# xiao-ble-e22-pcb-only.net
KiCad netlist of a schematic drawn in EAGLE
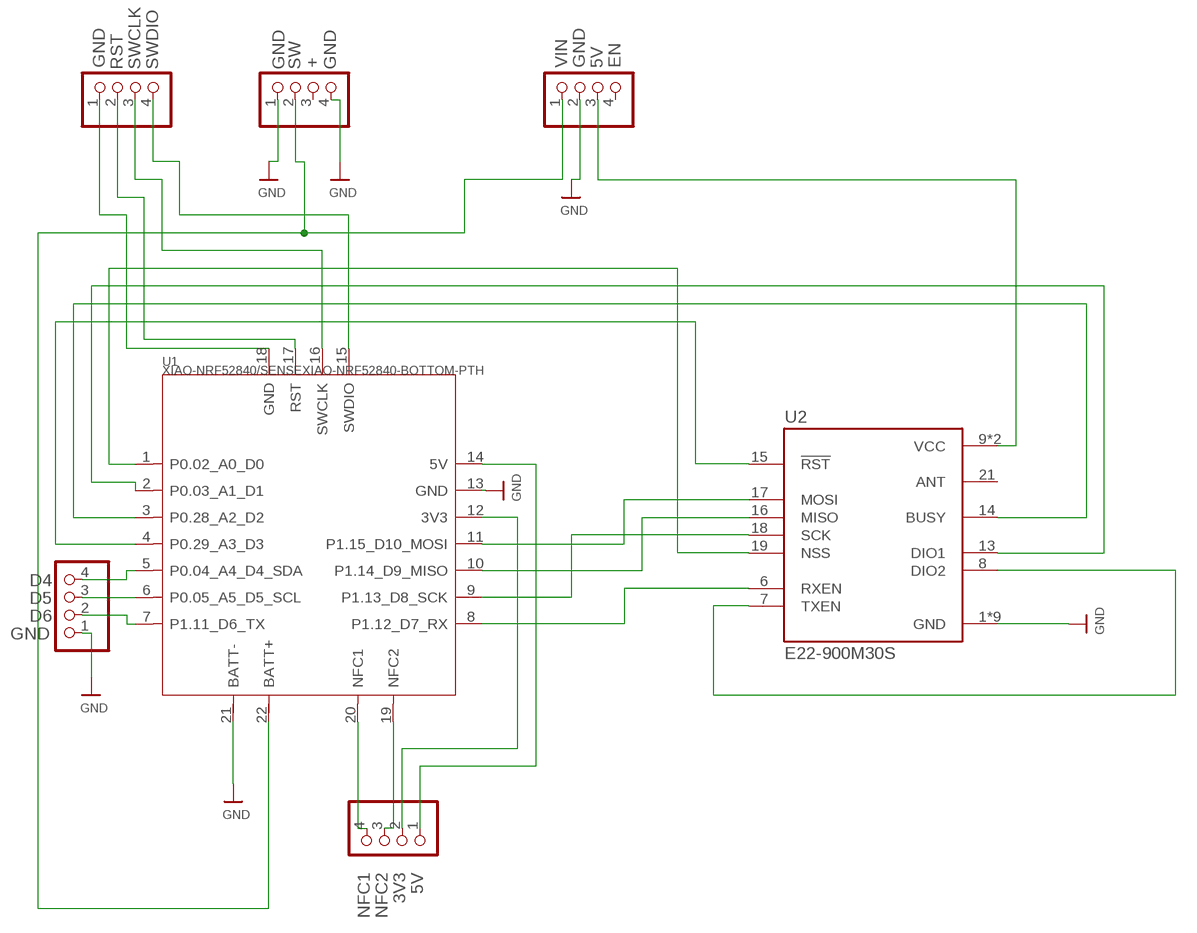
[diagram p0: schematic, sheet 1]

(export (version "E")
  (design (tool "Eeschema 10.0.6"))
  (components
    (comp (ref "JP1")
      (value "MiniBoost Breakout")
      (footprint "eagle-import:PADS-4")
      (fields
        (field (name "PIN_1") "VIN")
        (field (name "PIN_2") "GND")
        (field (name "PIN_3") "5V")
        (field (name "PIN_4") "EN")
      )
      (libsource (lib "eagle-import") (part "PADS-4"))
    )
    (comp (ref "JP2")
      (value "GPIO Breakout 1")
      (footprint "eagle-import:PADS-4")
      (fields
        (field (name "PIN_1") "5V")
        (field (name "PIN_2") "3V3")
        (field (name "PIN_3") "NFC2")
        (field (name "PIN_4") "NFC1")
      )
      (libsource (lib "eagle-import") (part "PADS-4"))
    )
    (comp (ref "JP3")
      (value "GPIO Breakout 2")
      (footprint "eagle-import:PADS-4")
      (fields
        (field (name "PIN_1") "GND")
        (field (name "PIN_2") "D6")
        (field (name "PIN_3") "D5")
        (field (name "PIN_4") "D4")
      )
      (libsource (lib "eagle-import") (part "PADS-4"))
    )
    (comp (ref "JP4")
      (value "JST + Switch Breakout")
      (footprint "eagle-import:PADS-4")
      (fields
        (field (name "PIN_1") "GND")
        (field (name "PIN_2") "+")
        (field (name "PIN_3") "SW")
        (field (name "PIN_4") "GND")
      )
      (libsource (lib "eagle-import") (part "PADS-4"))
    )
    (comp (ref "JP5")
      (value "GPIO Breakout 2")
      (footprint "eagle-import:PADS-4")
      (fields
        (field (name "PIN_1") "GND")
        (field (name "PIN_2") "RST")
        (field (name "PIN_3") "SWCLK")
        (field (name "PIN_4") "SWDIO")
      )
      (libsource (lib "eagle-import") (part "PADS-4"))
    )
    (comp (ref "U1")
      (value "XIAO-NRF52840/SENSEXIAO-NRF52840-BOTTOM-PTH")
      (footprint "eagle-import:XIAO-NRF52840_SENSE-MODULE14P-2.54-21X17.8MM-BOTTOM-PTH")
      (libsource (lib "eagle-import") (part "XIAO-NRF52840/SENSEXIAO-NRF52840-BOTTOM-PTH"))
    )
    (comp (ref "U2")
      (value "E22-900M30S")
      (footprint "eagle-import:XCVR_E22-900M30S")
      (fields (field (name "MF") "EBYTE"))
      (libsource (lib "eagle-import") (part "E22-900M30S"))
    )
  )
  (nets
    (net (code "1") (name "GND") (class "Default")
      (node (ref "JP1") (pin "2") (pinfunction "2_2") (pintype "passive"))
      (node (ref "JP3") (pin "1") (pinfunction "1_1") (pintype "passive"))
      (node (ref "JP4") (pin "1") (pinfunction "1_1") (pintype "passive"))
      (node (ref "JP4") (pin "4") (pinfunction "4_4") (pintype "passive"))
      (node (ref "U1") (pin "13") (pinfunction "GND_13") (pintype "bidirectional"))
      (node (ref "U1") (pin "21") (pinfunction "BATT-_21") (pintype "bidirectional"))
      (node (ref "U2") (pin "1") (pinfunction "GND_1") (pintype "power_in"))
      (node (ref "U2") (pin "11") (pinfunction "GND_11") (pintype "power_in"))
      (node (ref "U2") (pin "12") (pinfunction "GND_12") (pintype "power_in"))
      (node (ref "U2") (pin "2") (pinfunction "GND_2") (pintype "power_in"))
      (node (ref "U2") (pin "20") (pinfunction "GND_20") (pintype "power_in"))
      (node (ref "U2") (pin "22") (pinfunction "GND_22") (pintype "power_in"))
      (node (ref "U2") (pin "3") (pinfunction "GND_3") (pintype "power_in"))
      (node (ref "U2") (pin "4") (pinfunction "GND_4") (pintype "power_in"))
      (node (ref "U2") (pin "5") (pinfunction "GND_5") (pintype "power_in"))
    )
    (net (code "2") (name "Net-(JP1-Pad3)") (class "Default")
      (node (ref "JP1") (pin "3") (pinfunction "3_3") (pintype "passive"))
      (node (ref "U2") (pin "10") (pinfunction "VCC_10") (pintype "power_in"))
      (node (ref "U2") (pin "9") (pinfunction "VCC_9") (pintype "power_in"))
    )
    (net (code "3") (name "Net-(JP5-Pad1)") (class "Default")
      (node (ref "JP5") (pin "1") (pinfunction "1_1") (pintype "passive"))
      (node (ref "U1") (pin "18") (pinfunction "GND_18") (pintype "bidirectional"))
    )
    (net (code "4") (name "Net-(U1-3V3)") (class "Default")
      (node (ref "JP2") (pin "2") (pinfunction "2_2") (pintype "passive"))
      (node (ref "U1") (pin "12") (pinfunction "3V3_12") (pintype "bidirectional"))
    )
    (net (code "5") (name "Net-(U1-5V)") (class "Default")
      (node (ref "JP2") (pin "1") (pinfunction "1_1") (pintype "passive"))
      (node (ref "U1") (pin "14") (pinfunction "5V_14") (pintype "bidirectional"))
    )
    (net (code "6") (name "Net-(U1-BATT+)") (class "Default")
      (node (ref "JP1") (pin "1") (pinfunction "1_1") (pintype "passive"))
      (node (ref "JP4") (pin "2") (pinfunction "2_2") (pintype "passive"))
      (node (ref "U1") (pin "22") (pinfunction "BATT+_22") (pintype "bidirectional"))
    )
    (net (code "7") (name "Net-(U1-NFC1)") (class "Default")
      (node (ref "JP2") (pin "4") (pinfunction "4_4") (pintype "passive"))
      (node (ref "U1") (pin "20") (pinfunction "NFC1_20") (pintype "bidirectional"))
    )
    (net (code "8") (name "Net-(U1-NFC2)") (class "Default")
      (node (ref "JP2") (pin "3") (pinfunction "3_3") (pintype "passive"))
      (node (ref "U1") (pin "19") (pinfunction "NFC2_19") (pintype "bidirectional"))
    )
    (net (code "9") (name "Net-(U1-P0.02_A0_D0)") (class "Default")
      (node (ref "U1") (pin "1") (pinfunction "P0.02_A0_D0_1") (pintype "bidirectional"))
      (node (ref "U2") (pin "19") (pinfunction "NSS_19") (pintype "input"))
    )
    (net (code "10") (name "Net-(U1-P0.03_A1_D1)") (class "Default")
      (node (ref "U1") (pin "2") (pinfunction "P0.03_A1_D1_2") (pintype "bidirectional"))
      (node (ref "U2") (pin "13") (pinfunction "DIO1_13") (pintype "bidirectional"))
    )
    (net (code "11") (name "Net-(U1-P0.04_A4_D4_SDA)") (class "Default")
      (node (ref "JP3") (pin "4") (pinfunction "4_4") (pintype "passive"))
      (node (ref "U1") (pin "5") (pinfunction "P0.04_A4_D4_SDA_5") (pintype "bidirectional"))
    )
    (net (code "12") (name "Net-(U1-P0.05_A5_D5_SCL)") (class "Default")
      (node (ref "JP3") (pin "3") (pinfunction "3_3") (pintype "passive"))
      (node (ref "U1") (pin "6") (pinfunction "P0.05_A5_D5_SCL_6") (pintype "bidirectional"))
    )
    (net (code "13") (name "Net-(U1-P0.28_A2_D2)") (class "Default")
      (node (ref "U1") (pin "3") (pinfunction "P0.28_A2_D2_3") (pintype "bidirectional"))
      (node (ref "U2") (pin "14") (pinfunction "BUSY_14") (pintype "output"))
    )
    (net (code "14") (name "Net-(U1-P0.29_A3_D3)") (class "Default")
      (node (ref "U1") (pin "4") (pinfunction "P0.29_A3_D3_4") (pintype "bidirectional"))
      (node (ref "U2") (pin "15") (pinfunction "~{RST}_15") (pintype "input"))
    )
    (net (code "15") (name "Net-(U1-P1.11_D6_TX)") (class "Default")
      (node (ref "JP3") (pin "2") (pinfunction "2_2") (pintype "passive"))
      (node (ref "U1") (pin "7") (pinfunction "P1.11_D6_TX_7") (pintype "bidirectional"))
    )
    (net (code "16") (name "Net-(U1-P1.12_D7_RX)") (class "Default")
      (node (ref "U1") (pin "8") (pinfunction "P1.12_D7_RX_8") (pintype "bidirectional"))
      (node (ref "U2") (pin "6") (pinfunction "RXEN_6") (pintype "input"))
    )
    (net (code "17") (name "Net-(U1-P1.13_D8_SCK)") (class "Default")
      (node (ref "U1") (pin "9") (pinfunction "P1.13_D8_SCK_9") (pintype "bidirectional"))
      (node (ref "U2") (pin "18") (pinfunction "SCK_18") (pintype "input"))
    )
    (net (code "18") (name "Net-(U1-P1.14_D9_MISO)") (class "Default")
      (node (ref "U1") (pin "10") (pinfunction "P1.14_D9_MISO_10") (pintype "bidirectional"))
      (node (ref "U2") (pin "16") (pinfunction "MISO_16") (pintype "output"))
    )
    (net (code "19") (name "Net-(U1-P1.15_D10_MOSI)") (class "Default")
      (node (ref "U1") (pin "11") (pinfunction "P1.15_D10_MOSI_11") (pintype "bidirectional"))
      (node (ref "U2") (pin "17") (pinfunction "MOSI_17") (pintype "input"))
    )
    (net (code "20") (name "Net-(U1-RST)") (class "Default")
      (node (ref "JP5") (pin "2") (pinfunction "2_2") (pintype "passive"))
      (node (ref "U1") (pin "17") (pinfunction "RST_17") (pintype "bidirectional"))
    )
    (net (code "21") (name "Net-(U1-SWCLK)") (class "Default")
      (node (ref "JP5") (pin "3") (pinfunction "3_3") (pintype "passive"))
      (node (ref "U1") (pin "16") (pinfunction "SWCLK_16") (pintype "bidirectional"))
    )
    (net (code "22") (name "Net-(U1-SWDIO)") (class "Default")
      (node (ref "JP5") (pin "4") (pinfunction "4_4") (pintype "passive"))
      (node (ref "U1") (pin "15") (pinfunction "SWDIO_15") (pintype "bidirectional"))
    )
    (net (code "23") (name "Net-(U2-DIO2)") (class "Default")
      (node (ref "U2") (pin "7") (pinfunction "TXEN_7") (pintype "input"))
      (node (ref "U2") (pin "8") (pinfunction "DIO2_8") (pintype "bidirectional"))
    )
    (net (code "24") (name "unconnected-(JP1-Pad4)") (class "Default")
      (node (ref "JP1") (pin "4") (pinfunction "4_4") (pintype "passive"))
    )
    (net (code "25") (name "unconnected-(JP4-Pad3)") (class "Default")
      (node (ref "JP4") (pin "3") (pinfunction "3_3") (pintype "passive"))
    )
    (net (code "26") (name "unconnected-(U2-ANT-Pad21)") (class "Default")
      (node (ref "U2") (pin "21") (pinfunction "ANT_21") (pintype "output"))
    )
  )
)
